# burnerindicator.net
KiCad netlist of a schematic drawn in EAGLE
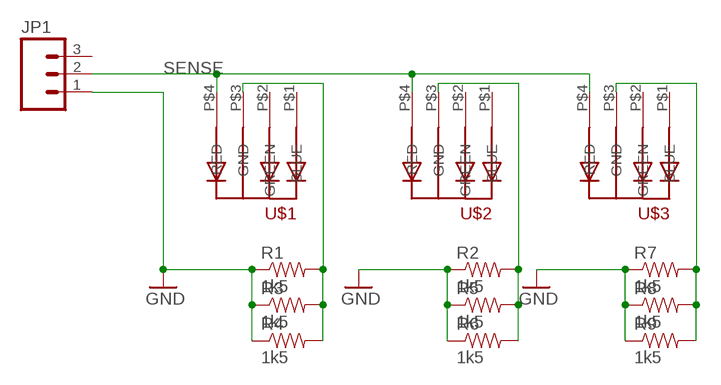
[diagram p0: schematic, sheet 1]

(export (version "E")
  (design (tool "Eeschema 10.0.6"))
  (components
    (comp (ref "JP1")
      (value "M03POLAR_LOCK")
      (footprint "eagle-import:MOLEX-1X3_LOCK")
      (libsource (lib "eagle-import") (part "M03POLAR_LOCK"))
    )
    (comp (ref "R1")
      (value "1k5")
      (footprint "eagle-import:0603-RES")
      (libsource (lib "eagle-import") (part "RESISTOR0603-RES"))
    )
    (comp (ref "R2")
      (value "1k5")
      (footprint "eagle-import:0603-RES")
      (libsource (lib "eagle-import") (part "RESISTOR0603-RES"))
    )
    (comp (ref "R3")
      (value "1k5")
      (footprint "eagle-import:0603-RES")
      (libsource (lib "eagle-import") (part "RESISTOR0603-RES"))
    )
    (comp (ref "R4")
      (value "1k5")
      (footprint "eagle-import:0603-RES")
      (libsource (lib "eagle-import") (part "RESISTOR0603-RES"))
    )
    (comp (ref "R5")
      (value "1k5")
      (footprint "eagle-import:0603-RES")
      (libsource (lib "eagle-import") (part "RESISTOR0603-RES"))
    )
    (comp (ref "R6")
      (value "1k5")
      (footprint "eagle-import:0603-RES")
      (libsource (lib "eagle-import") (part "RESISTOR0603-RES"))
    )
    (comp (ref "R7")
      (value "1k5")
      (footprint "eagle-import:0603-RES")
      (libsource (lib "eagle-import") (part "RESISTOR0603-RES"))
    )
    (comp (ref "R8")
      (value "1k5")
      (footprint "eagle-import:0603-RES")
      (libsource (lib "eagle-import") (part "RESISTOR0603-RES"))
    )
    (comp (ref "R9")
      (value "1k5")
      (footprint "eagle-import:0603-RES")
      (libsource (lib "eagle-import") (part "RESISTOR0603-RES"))
    )
    (comp (ref "U$1")
      (value "5MMRGBLED")
      (footprint "eagle-import:LED5MMRGB")
      (libsource (lib "eagle-import") (part "5MMRGBLED"))
    )
    (comp (ref "U$2")
      (value "5MMRGBLED")
      (footprint "eagle-import:LED5MMRGB")
      (libsource (lib "eagle-import") (part "5MMRGBLED"))
    )
    (comp (ref "U$3")
      (value "5MMRGBLED")
      (footprint "eagle-import:LED5MMRGB")
      (libsource (lib "eagle-import") (part "5MMRGBLED"))
    )
  )
  (nets
    (net (code "1") (name "/SENSE") (class "Default")
      (node (ref "JP1") (pin "2") (pinfunction "2_2") (pintype "passive"))
      (node (ref "U$1") (pin "P$4") (pinfunction "RED_P$4") (pintype "bidirectional"))
      (node (ref "U$2") (pin "P$4") (pinfunction "RED_P$4") (pintype "bidirectional"))
      (node (ref "U$3") (pin "P$4") (pinfunction "RED_P$4") (pintype "bidirectional"))
    )
    (net (code "2") (name "GND") (class "Default")
      (node (ref "JP1") (pin "1") (pinfunction "1_1") (pintype "passive"))
      (node (ref "R1") (pin "1") (pinfunction "1_1") (pintype "passive"))
      (node (ref "R2") (pin "1") (pinfunction "1_1") (pintype "passive"))
      (node (ref "R3") (pin "1") (pinfunction "1_1") (pintype "passive"))
      (node (ref "R4") (pin "1") (pinfunction "1_1") (pintype "passive"))
      (node (ref "R5") (pin "1") (pinfunction "1_1") (pintype "passive"))
      (node (ref "R6") (pin "1") (pinfunction "1_1") (pintype "passive"))
      (node (ref "R7") (pin "1") (pinfunction "1_1") (pintype "passive"))
      (node (ref "R8") (pin "1") (pinfunction "1_1") (pintype "passive"))
      (node (ref "R9") (pin "1") (pinfunction "1_1") (pintype "passive"))
    )
    (net (code "3") (name "Net-(U$1-GND)") (class "Default")
      (node (ref "R1") (pin "2") (pinfunction "2_2") (pintype "passive"))
      (node (ref "R3") (pin "2") (pinfunction "2_2") (pintype "passive"))
      (node (ref "R4") (pin "2") (pinfunction "2_2") (pintype "passive"))
      (node (ref "U$1") (pin "P$3") (pinfunction "GND_P$3") (pintype "bidirectional"))
    )
    (net (code "4") (name "Net-(U$2-GND)") (class "Default")
      (node (ref "R2") (pin "2") (pinfunction "2_2") (pintype "passive"))
      (node (ref "R5") (pin "2") (pinfunction "2_2") (pintype "passive"))
      (node (ref "R6") (pin "2") (pinfunction "2_2") (pintype "passive"))
      (node (ref "U$2") (pin "P$3") (pinfunction "GND_P$3") (pintype "bidirectional"))
    )
    (net (code "5") (name "Net-(U$3-GND)") (class "Default")
      (node (ref "R7") (pin "2") (pinfunction "2_2") (pintype "passive"))
      (node (ref "R8") (pin "2") (pinfunction "2_2") (pintype "passive"))
      (node (ref "R9") (pin "2") (pinfunction "2_2") (pintype "passive"))
      (node (ref "U$3") (pin "P$3") (pinfunction "GND_P$3") (pintype "bidirectional"))
    )
    (net (code "6") (name "unconnected-(JP1-Pad3)") (class "Default")
      (node (ref "JP1") (pin "3") (pinfunction "3_3") (pintype "passive"))
    )
    (net (code "7") (name "unconnected-(U$1-BLUE-PadP$1)") (class "Default")
      (node (ref "U$1") (pin "P$1") (pinfunction "BLUE_P$1") (pintype "bidirectional"))
    )
    (net (code "8") (name "unconnected-(U$1-GREEN-PadP$2)") (class "Default")
      (node (ref "U$1") (pin "P$2") (pinfunction "GREEN_P$2") (pintype "bidirectional"))
    )
    (net (code "9") (name "unconnected-(U$2-BLUE-PadP$1)") (class "Default")
      (node (ref "U$2") (pin "P$1") (pinfunction "BLUE_P$1") (pintype "bidirectional"))
    )
    (net (code "10") (name "unconnected-(U$2-GREEN-PadP$2)") (class "Default")
      (node (ref "U$2") (pin "P$2") (pinfunction "GREEN_P$2") (pintype "bidirectional"))
    )
    (net (code "11") (name "unconnected-(U$3-BLUE-PadP$1)") (class "Default")
      (node (ref "U$3") (pin "P$1") (pinfunction "BLUE_P$1") (pintype "bidirectional"))
    )
    (net (code "12") (name "unconnected-(U$3-GREEN-PadP$2)") (class "Default")
      (node (ref "U$3") (pin "P$2") (pinfunction "GREEN_P$2") (pintype "bidirectional"))
    )
  )
)
